# schematic_Easy_EDA_project.net
KiCad netlist of a schematic drawn in EasyEDA
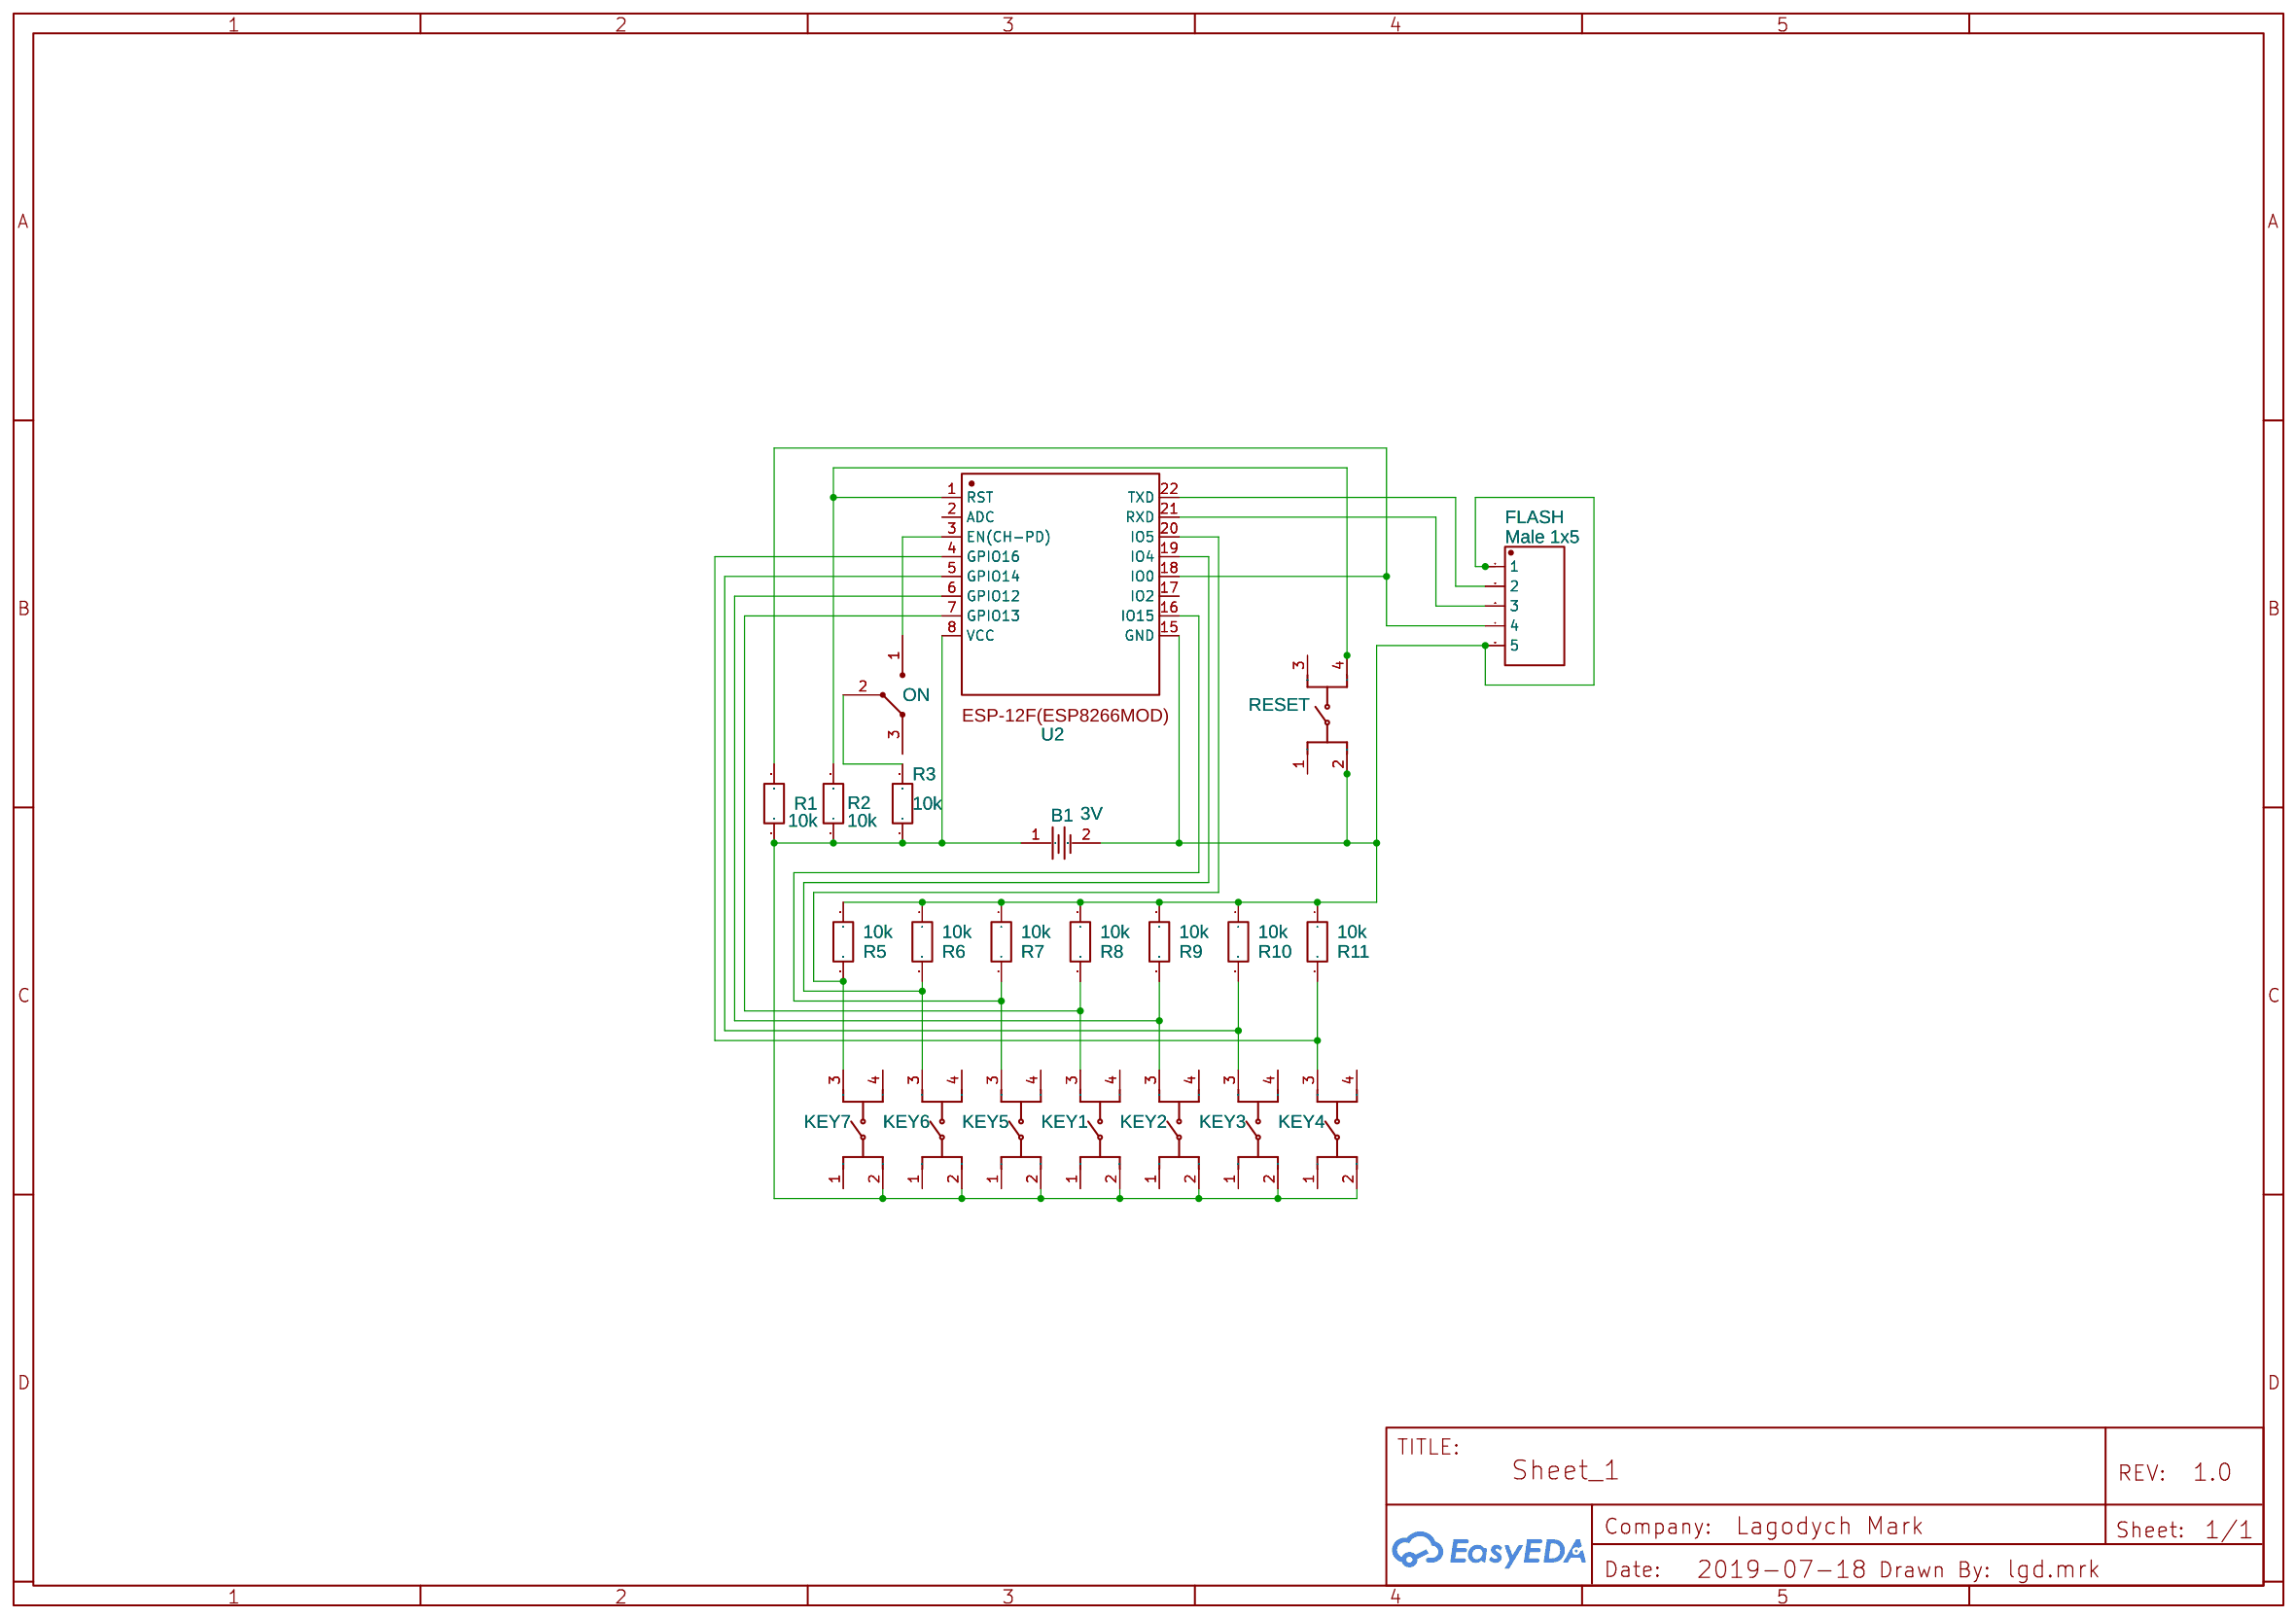
[diagram p0: schematic sheet]

(export (version "E")
  (design (tool "Eeschema 10.0.6"))
  (components
    (comp (ref "B1")
      (value "3V")
      (fields (field (name "BOM_Manufacturer Part") "BS-2-1") (field (name "BOM_Supplier Part") "C70376"))
      (libsource (lib "") (part "Unknown_530_420"))
    )
    (comp (ref "FLASH")
      (value "Male 1x5")
      (fields
        (field (name "BOM_Manufacturer Part") "210S-1*5P L=11.6MMGold-plated black")
        (field (name "BOM_Supplier Part") "C124379")
      )
      (libsource (lib "") (part "Unknown_765_300"))
    )
    (comp (ref "KEY1")
      (value "TS-1102-5016")
      (fields (field (name "BOM_Supplier Part") "C111609"))
      (libsource (lib "") (part "Unknown_545_565"))
    )
    (comp (ref "KEY2")
      (value "TS-1102-5016")
      (fields (field (name "BOM_Supplier Part") "C111609"))
      (libsource (lib "") (part "Unknown_585_565"))
    )
    (comp (ref "KEY3")
      (value "TS-1102-5016")
      (fields (field (name "BOM_Supplier Part") "C111609"))
      (libsource (lib "") (part "Unknown_625_565"))
    )
    (comp (ref "KEY4")
      (value "TS-1102-5016")
      (fields (field (name "BOM_Supplier Part") "C111609"))
      (libsource (lib "") (part "Unknown_665_565"))
    )
    (comp (ref "KEY5")
      (value "TS-1102-5016")
      (fields (field (name "BOM_Supplier Part") "C111609"))
      (libsource (lib "") (part "Unknown_505_565"))
    )
    (comp (ref "KEY6")
      (value "TS-1102-5016")
      (fields (field (name "BOM_Supplier Part") "C111609"))
      (libsource (lib "") (part "Unknown_465_565"))
    )
    (comp (ref "KEY7")
      (value "TS-1102-5016")
      (fields (field (name "BOM_Supplier Part") "C111609"))
      (libsource (lib "") (part "Unknown_425_565"))
    )
    (comp (ref "ON") (value "SIMPLE SWITCH") (libsource (lib "") (part "Unknown_450_345")))
    (comp (ref "R1")
      (value "10k")
      (fields (field (name "BOM_Manufacturer Part") "?"))
      (libsource (lib "") (part "Res_AXIAL-0.3(1/8W)_EU_1"))
    )
    (comp (ref "R2")
      (value "10k")
      (fields (field (name "BOM_Manufacturer Part") "?"))
      (libsource (lib "") (part "Res_AXIAL-0.3(1/8W)_EU_1"))
    )
    (comp (ref "R3")
      (value "10k")
      (fields (field (name "BOM_Manufacturer Part") "?"))
      (libsource (lib "") (part "Res_AXIAL-0.3(1/8W)_EU_1"))
    )
    (comp (ref "R5")
      (value "10k")
      (fields (field (name "BOM_Manufacturer Part") "?"))
      (libsource (lib "") (part "Res_AXIAL-0.3(1/8W)_EU"))
    )
    (comp (ref "R6")
      (value "10k")
      (fields (field (name "BOM_Manufacturer Part") "?"))
      (libsource (lib "") (part "Res_AXIAL-0.3(1/8W)_EU"))
    )
    (comp (ref "R7")
      (value "10k")
      (fields (field (name "BOM_Manufacturer Part") "?"))
      (libsource (lib "") (part "Res_AXIAL-0.3(1/8W)_EU"))
    )
    (comp (ref "R8")
      (value "10k")
      (fields (field (name "BOM_Manufacturer Part") "?"))
      (libsource (lib "") (part "Res_AXIAL-0.3(1/8W)_EU"))
    )
    (comp (ref "R9")
      (value "10k")
      (fields (field (name "BOM_Manufacturer Part") "?"))
      (libsource (lib "") (part "Res_AXIAL-0.3(1/8W)_EU"))
    )
    (comp (ref "R10")
      (value "10k")
      (fields (field (name "BOM_Manufacturer Part") "?"))
      (libsource (lib "") (part "Res_AXIAL-0.3(1/8W)_EU"))
    )
    (comp (ref "R11")
      (value "10k")
      (fields (field (name "BOM_Manufacturer Part") "?"))
      (libsource (lib "") (part "Res_AXIAL-0.3(1/8W)_EU"))
    )
    (comp (ref "RESET")
      (value "TS-1102-5016")
      (fields (field (name "BOM_Supplier Part") "C111609"))
      (libsource (lib "") (part "Unknown_660_355"))
    )
    (comp (ref "U2")
      (value "esp8266-12")
      (fields (field (name "BOM_Manufacturer Part") "New SchematicLib"))
      (libsource (lib "") (part "Unknown_530_285"))
    )
  )
  (nets
    (net (code "1") (name "Net-(ON-Pad2)") (class "Default")
      (node (ref "ON") (pin "2") (pintype "unspecified"))
      (node (ref "R3") (pin "2") (pinfunction "2_2") (pintype "unspecified"))
    )
    (net (code "2") (name "Net-(U2-EN(CH-PD))") (class "Default")
      (node (ref "ON") (pin "1") (pintype "unspecified"))
      (node (ref "U2") (pin "3") (pinfunction "EN(CH-PD)_3") (pintype "unspecified"))
    )
    (net (code "3") (name "Net-(U2-GND)") (class "Default")
      (node (ref "B1") (pin "2") (pinfunction "2_2") (pintype "input"))
      (node (ref "FLASH") (pin "1") (pinfunction "1_1") (pintype "unspecified"))
      (node (ref "FLASH") (pin "5") (pinfunction "5_5") (pintype "unspecified"))
      (node (ref "R10") (pin "1") (pinfunction "1_1") (pintype "unspecified"))
      (node (ref "R11") (pin "1") (pinfunction "1_1") (pintype "unspecified"))
      (node (ref "R5") (pin "1") (pinfunction "1_1") (pintype "unspecified"))
      (node (ref "R6") (pin "1") (pinfunction "1_1") (pintype "unspecified"))
      (node (ref "R7") (pin "1") (pinfunction "1_1") (pintype "unspecified"))
      (node (ref "R8") (pin "1") (pinfunction "1_1") (pintype "unspecified"))
      (node (ref "R9") (pin "1") (pinfunction "1_1") (pintype "unspecified"))
      (node (ref "RESET") (pin "2") (pinfunction "2_2") (pintype "unspecified"))
      (node (ref "U2") (pin "15") (pinfunction "GND_15") (pintype "unspecified"))
    )
    (net (code "4") (name "Net-(U2-GPIO12)") (class "Default")
      (node (ref "KEY2") (pin "3") (pinfunction "3_3") (pintype "unspecified"))
      (node (ref "R9") (pin "2") (pinfunction "2_2") (pintype "unspecified"))
      (node (ref "U2") (pin "6") (pinfunction "GPIO12_6") (pintype "unspecified"))
    )
    (net (code "5") (name "Net-(U2-GPIO13)") (class "Default")
      (node (ref "KEY1") (pin "3") (pinfunction "3_3") (pintype "unspecified"))
      (node (ref "R8") (pin "2") (pinfunction "2_2") (pintype "unspecified"))
      (node (ref "U2") (pin "7") (pinfunction "GPIO13_7") (pintype "unspecified"))
    )
    (net (code "6") (name "Net-(U2-GPIO14)") (class "Default")
      (node (ref "KEY3") (pin "3") (pinfunction "3_3") (pintype "unspecified"))
      (node (ref "R10") (pin "2") (pinfunction "2_2") (pintype "unspecified"))
      (node (ref "U2") (pin "5") (pinfunction "GPIO14_5") (pintype "unspecified"))
    )
    (net (code "7") (name "Net-(U2-GPIO16)") (class "Default")
      (node (ref "KEY4") (pin "3") (pinfunction "3_3") (pintype "unspecified"))
      (node (ref "R11") (pin "2") (pinfunction "2_2") (pintype "unspecified"))
      (node (ref "U2") (pin "4") (pinfunction "GPIO16_4") (pintype "unspecified"))
    )
    (net (code "8") (name "Net-(U2-IO0)") (class "Default")
      (node (ref "FLASH") (pin "4") (pinfunction "4_4") (pintype "unspecified"))
      (node (ref "R1") (pin "2") (pinfunction "2_2") (pintype "unspecified"))
      (node (ref "U2") (pin "18") (pinfunction "IO0_18") (pintype "unspecified"))
    )
    (net (code "9") (name "Net-(U2-IO4)") (class "Default")
      (node (ref "KEY6") (pin "3") (pinfunction "3_3") (pintype "unspecified"))
      (node (ref "R6") (pin "2") (pinfunction "2_2") (pintype "unspecified"))
      (node (ref "U2") (pin "19") (pinfunction "IO4_19") (pintype "unspecified"))
    )
    (net (code "10") (name "Net-(U2-IO5)") (class "Default")
      (node (ref "KEY7") (pin "3") (pinfunction "3_3") (pintype "unspecified"))
      (node (ref "R5") (pin "2") (pinfunction "2_2") (pintype "unspecified"))
      (node (ref "U2") (pin "20") (pinfunction "IO5_20") (pintype "unspecified"))
    )
    (net (code "11") (name "Net-(U2-IO15)") (class "Default")
      (node (ref "KEY5") (pin "3") (pinfunction "3_3") (pintype "unspecified"))
      (node (ref "R7") (pin "2") (pinfunction "2_2") (pintype "unspecified"))
      (node (ref "U2") (pin "16") (pinfunction "IO15_16") (pintype "unspecified"))
    )
    (net (code "12") (name "Net-(U2-RST)") (class "Default")
      (node (ref "R2") (pin "2") (pinfunction "2_2") (pintype "unspecified"))
      (node (ref "RESET") (pin "4") (pinfunction "4_4") (pintype "unspecified"))
      (node (ref "U2") (pin "1") (pinfunction "RST_1") (pintype "unspecified"))
    )
    (net (code "13") (name "Net-(U2-RXD)") (class "Default")
      (node (ref "FLASH") (pin "3") (pinfunction "3_3") (pintype "unspecified"))
      (node (ref "U2") (pin "21") (pinfunction "RXD_21") (pintype "unspecified"))
    )
    (net (code "14") (name "Net-(U2-TXD)") (class "Default")
      (node (ref "FLASH") (pin "2") (pinfunction "2_2") (pintype "unspecified"))
      (node (ref "U2") (pin "22") (pinfunction "TXD_22") (pintype "unspecified"))
    )
    (net (code "15") (name "Net-(U2-VCC)") (class "Default")
      (node (ref "B1") (pin "1") (pinfunction "1_1") (pintype "input"))
      (node (ref "KEY1") (pin "2") (pinfunction "2_2") (pintype "unspecified"))
      (node (ref "KEY2") (pin "2") (pinfunction "2_2") (pintype "unspecified"))
      (node (ref "KEY3") (pin "2") (pinfunction "2_2") (pintype "unspecified"))
      (node (ref "KEY4") (pin "2") (pinfunction "2_2") (pintype "unspecified"))
      (node (ref "KEY5") (pin "2") (pinfunction "2_2") (pintype "unspecified"))
      (node (ref "KEY6") (pin "2") (pinfunction "2_2") (pintype "unspecified"))
      (node (ref "KEY7") (pin "2") (pinfunction "2_2") (pintype "unspecified"))
      (node (ref "R1") (pin "1") (pinfunction "1_1") (pintype "unspecified"))
      (node (ref "R2") (pin "1") (pinfunction "1_1") (pintype "unspecified"))
      (node (ref "R3") (pin "1") (pinfunction "1_1") (pintype "unspecified"))
      (node (ref "U2") (pin "8") (pinfunction "VCC_8") (pintype "unspecified"))
    )
    (net (code "16") (name "unconnected-(KEY1-Pad1)") (class "Default")
      (node (ref "KEY1") (pin "1") (pinfunction "1_1") (pintype "unspecified"))
    )
    (net (code "17") (name "unconnected-(KEY1-Pad4)") (class "Default")
      (node (ref "KEY1") (pin "4") (pinfunction "4_4") (pintype "unspecified"))
    )
    (net (code "18") (name "unconnected-(KEY2-Pad1)") (class "Default")
      (node (ref "KEY2") (pin "1") (pinfunction "1_1") (pintype "unspecified"))
    )
    (net (code "19") (name "unconnected-(KEY2-Pad4)") (class "Default")
      (node (ref "KEY2") (pin "4") (pinfunction "4_4") (pintype "unspecified"))
    )
    (net (code "20") (name "unconnected-(KEY3-Pad1)") (class "Default")
      (node (ref "KEY3") (pin "1") (pinfunction "1_1") (pintype "unspecified"))
    )
    (net (code "21") (name "unconnected-(KEY3-Pad4)") (class "Default")
      (node (ref "KEY3") (pin "4") (pinfunction "4_4") (pintype "unspecified"))
    )
    (net (code "22") (name "unconnected-(KEY4-Pad1)") (class "Default")
      (node (ref "KEY4") (pin "1") (pinfunction "1_1") (pintype "unspecified"))
    )
    (net (code "23") (name "unconnected-(KEY4-Pad4)") (class "Default")
      (node (ref "KEY4") (pin "4") (pinfunction "4_4") (pintype "unspecified"))
    )
    (net (code "24") (name "unconnected-(KEY5-Pad1)") (class "Default")
      (node (ref "KEY5") (pin "1") (pinfunction "1_1") (pintype "unspecified"))
    )
    (net (code "25") (name "unconnected-(KEY5-Pad4)") (class "Default")
      (node (ref "KEY5") (pin "4") (pinfunction "4_4") (pintype "unspecified"))
    )
    (net (code "26") (name "unconnected-(KEY6-Pad1)") (class "Default")
      (node (ref "KEY6") (pin "1") (pinfunction "1_1") (pintype "unspecified"))
    )
    (net (code "27") (name "unconnected-(KEY6-Pad4)") (class "Default")
      (node (ref "KEY6") (pin "4") (pinfunction "4_4") (pintype "unspecified"))
    )
    (net (code "28") (name "unconnected-(KEY7-Pad1)") (class "Default")
      (node (ref "KEY7") (pin "1") (pinfunction "1_1") (pintype "unspecified"))
    )
    (net (code "29") (name "unconnected-(KEY7-Pad4)") (class "Default")
      (node (ref "KEY7") (pin "4") (pinfunction "4_4") (pintype "unspecified"))
    )
    (net (code "30") (name "unconnected-(ON-Pad3)") (class "Default")
      (node (ref "ON") (pin "3") (pintype "unspecified"))
    )
    (net (code "31") (name "unconnected-(RESET-Pad1)") (class "Default")
      (node (ref "RESET") (pin "1") (pinfunction "1_1") (pintype "unspecified"))
    )
    (net (code "32") (name "unconnected-(RESET-Pad3)") (class "Default")
      (node (ref "RESET") (pin "3") (pinfunction "3_3") (pintype "unspecified"))
    )
    (net (code "33") (name "unconnected-(U2-ADC-Pad2)") (class "Default")
      (node (ref "U2") (pin "2") (pinfunction "ADC_2") (pintype "unspecified"))
    )
    (net (code "34") (name "unconnected-(U2-IO2-Pad17)") (class "Default")
      (node (ref "U2") (pin "17") (pinfunction "IO2_17") (pintype "unspecified"))
    )
  )
)
